# 89C51.net
KiCad netlist of a schematic drawn in Altium Designer
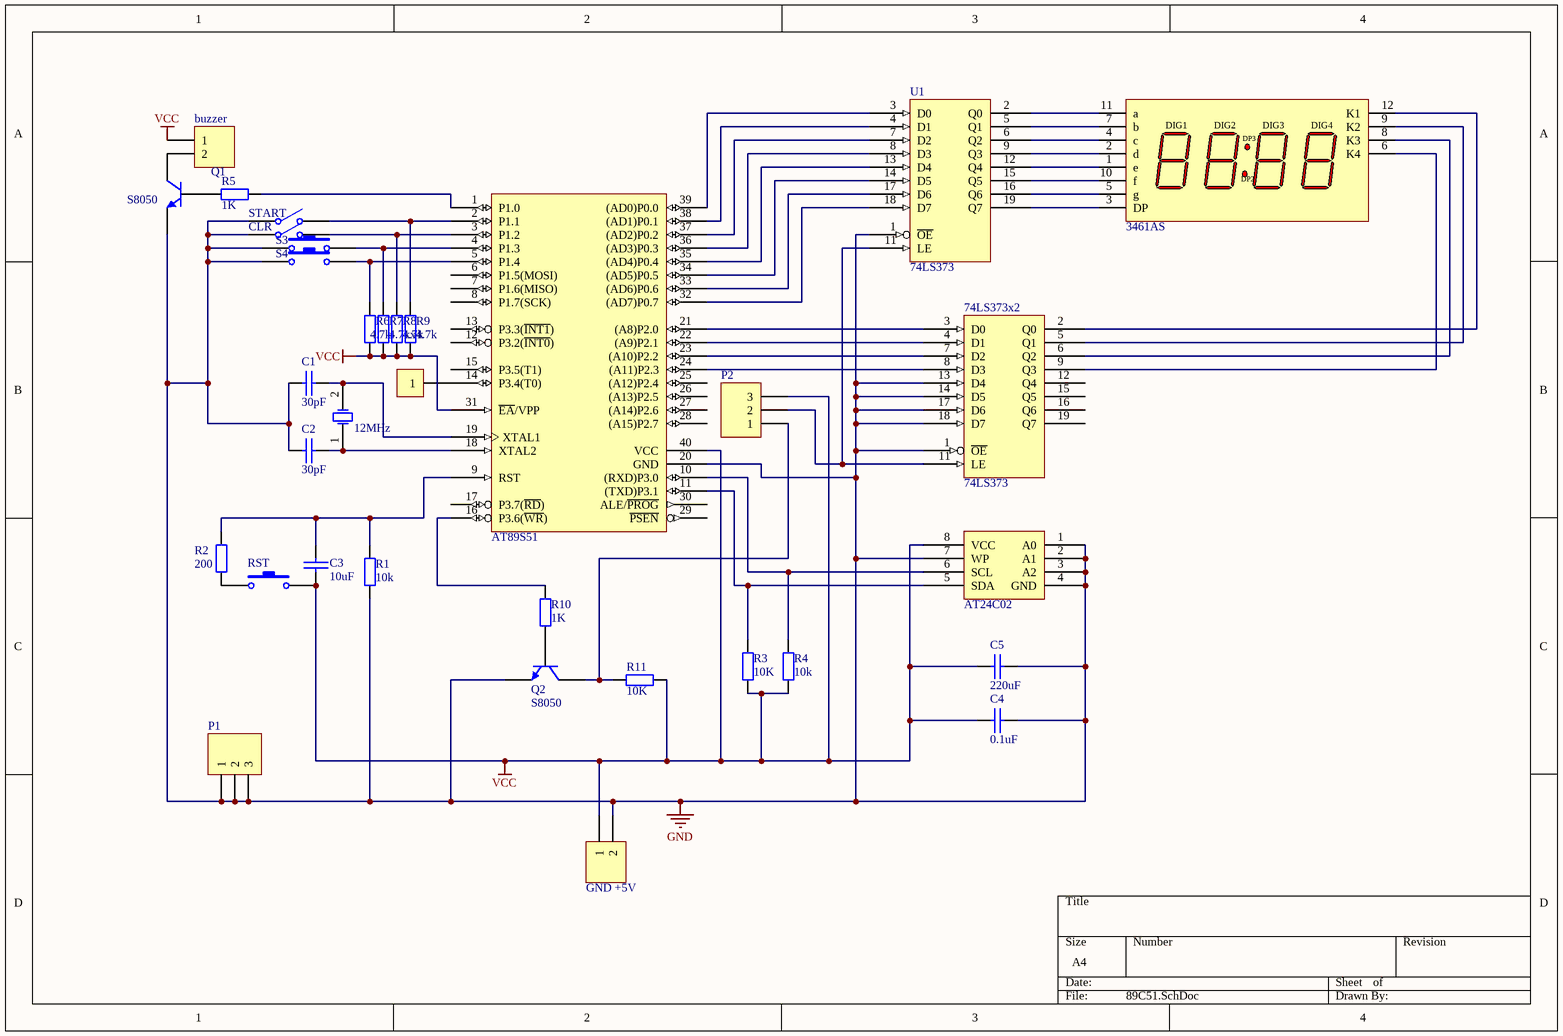
[diagram p0: 89C51.SchDoc]

(export (version "E")
  (design (tool "Eeschema 10.0.6"))
  (components
    (comp (ref "74LS373x2")
      (value "74LS373")
      (footprint "DIP-20")
      (libsource (lib "Protel DOS Schematic TTL") (part "74LS373"))
    )
    (comp (ref "89S51")
      (value "AT89S51")
      (footprint "DIP-40")
      (description "8-Bit Microcontroller with 4K ISP Flash ROM")
      (libsource (lib "Atmel Microcontroller 8051 Architecture") (part "AT89S51"))
    )
    (comp (ref "buzzer")
      (value "Header 2")
      (footprint "BUZZER")
      (description "Header, 2-Pin")
      (fields (field (name "PUBLISHER") "Altium Limited"))
      (libsource (lib "") (part "Header 2_1"))
    )
    (comp (ref "C1")
      (value "30pF")
      (footprint "RAD-0.1")
      (description "Capacitor")
      (libsource (lib "Miscellaneous Devices") (part "CAP"))
    )
    (comp (ref "C2")
      (value "30pF")
      (footprint "RAD-0.1")
      (description "Capacitor")
      (libsource (lib "Miscellaneous Devices") (part "CAP"))
    )
    (comp (ref "C3")
      (value "10uF")
      (footprint "RB.2/.1")
      (description "Capacitor")
      (libsource (lib "Miscellaneous Devices") (part "CAP"))
    )
    (comp (ref "C4")
      (value "0.1uF")
      (footprint "RAD-0.1")
      (description "Capacitor")
      (libsource (lib "Miscellaneous Devices") (part "CAP"))
    )
    (comp (ref "C5")
      (value "220uF")
      (footprint "RB.2/.2")
      (description "Capacitor")
      (libsource (lib "Miscellaneous Devices") (part "CAP"))
    )
    (comp (ref "CLR")
      (value "~")
      (footprint "push_switch")
      (description "Single-Pole, Single-Throw Switch")
      (fields (field (name "PUBLISHER") "Altium Limited"))
      (libsource (lib "Miscellaneous Devices") (part "SW-SPST"))
    )
    (comp (ref "Disp")
      (value "3461AS")
      (footprint "3461AS")
      (description "14.22 mm GaP HER, Untinted, 88:88 4-Digit 7-Segment Display: CC, Gray Surface")
      (fields (field (name "PUBLISHER") "Altium Limited"))
      (libsource (lib "Agilent LED Display 7-Segment, 4-Digit") (part "HDSP-B03E"))
    )
    (comp (ref "GND +5V")
      (value "Header 2")
      (footprint "POWER PLUG2")
      (description "Header, 2-Pin")
      (fields (field (name "PUBLISHER") "Altium Limited"))
      (libsource (lib "Miscellaneous Connectors") (part "Header 2"))
    )
    (comp (ref "header1") (value "HDR_1") (footprint "HDR_1") (libsource (lib "for_use") (part "HDR_1")))
    (comp (ref "P1")
      (value "Header 3")
      (footprint "HDR1X3")
      (description "Header, 3-Pin")
      (fields (field (name "PUBLISHER") "Altium Limited"))
      (libsource (lib "Miscellaneous Connectors") (part "Header 3"))
    )
    (comp (ref "P2")
      (value "Header 3")
      (footprint "HDR1X3")
      (description "Header, 3-Pin")
      (fields (field (name "PUBLISHER") "Altium Limited"))
      (libsource (lib "") (part "Header 3_1"))
    )
    (comp (ref "Q1")
      (value "S8050")
      (footprint "NPN-2")
      (description "NPN General Purpose Amplifier")
      (fields (field (name "PUBLISHER") "Altium Limited"))
      (libsource (lib "Miscellaneous Devices") (part "2N3904"))
    )
    (comp (ref "Q2")
      (value "S8050")
      (footprint "NPN-2")
      (description "NPN General Purpose Amplifier")
      (fields (field (name "PUBLISHER") "Altium Limited"))
      (libsource (lib "") (part "2N3904_1"))
    )
    (comp (ref "R1")
      (value "10k")
      (footprint "AXIAL-0.4")
      (description "Resistor")
      (fields (field (name "COMMENT_1") "10k") (field (name "PUBLISHER") "Altium Limited"))
      (libsource (lib "Miscellaneous Devices") (part "Res2"))
    )
    (comp (ref "R2")
      (value "200")
      (footprint "AXIAL-0.4")
      (description "Resistor")
      (fields (field (name "PUBLISHER") "Altium Limited"))
      (libsource (lib "Miscellaneous Devices") (part "Res2"))
    )
    (comp (ref "R3")
      (value "10K")
      (footprint "AXIAL-0.4")
      (description "Resistor")
      (fields (field (name "PUBLISHER") "Altium Limited"))
      (libsource (lib "Miscellaneous Devices") (part "Res2"))
    )
    (comp (ref "R4")
      (value "10k")
      (footprint "AXIAL-0.4")
      (description "Resistor")
      (fields (field (name "Comment") "10K") (field (name "PUBLISHER") "Altium Limited"))
      (libsource (lib "Miscellaneous Devices") (part "Res2"))
    )
    (comp (ref "R5")
      (value "1K")
      (footprint "AXIAL-0.4")
      (description "Resistor")
      (fields (field (name "PUBLISHER") "Altium Limited"))
      (libsource (lib "") (part "Res2_1"))
    )
    (comp (ref "R6")
      (value "4.7k")
      (footprint "AXIAL-0.4")
      (description "Resistor")
      (fields (field (name "PUBLISHER") "Altium Limited"))
      (libsource (lib "Miscellaneous Devices") (part "Res2"))
    )
    (comp (ref "R7")
      (value "4.7kx4")
      (footprint "AXIAL-0.4")
      (description "Resistor")
      (fields (field (name "PUBLISHER") "Altium Limited"))
      (libsource (lib "Miscellaneous Devices") (part "Res2"))
    )
    (comp (ref "R8")
      (value "4.7k")
      (footprint "AXIAL-0.4")
      (description "Resistor")
      (fields (field (name "PUBLISHER") "Altium Limited"))
      (libsource (lib "Miscellaneous Devices") (part "Res2"))
    )
    (comp (ref "R9")
      (value "4.7k")
      (footprint "AXIAL-0.4")
      (description "Resistor")
      (fields (field (name "PUBLISHER") "Altium Limited"))
      (libsource (lib "Miscellaneous Devices") (part "Res2"))
    )
    (comp (ref "R10")
      (value "1K")
      (footprint "AXIAL-0.4")
      (description "Resistor")
      (fields (field (name "PUBLISHER") "Altium Limited"))
      (libsource (lib "Miscellaneous Devices") (part "Res2"))
    )
    (comp (ref "R11")
      (value "10K")
      (footprint "AXIAL-0.4")
      (description "Resistor")
      (fields (field (name "PUBLISHER") "Altium Limited"))
      (libsource (lib "") (part "Res2_2"))
    )
    (comp (ref "RST")
      (value "SW-PB")
      (footprint "AN-S")
      (description "Switch")
      (fields (field (name "PUBLISHER") "Altium Limited"))
      (libsource (lib "Miscellaneous Devices") (part "SW-PB"))
    )
    (comp (ref "S3")
      (value "SW-PB")
      (footprint "AN-S")
      (description "Switch")
      (fields (field (name "PUBLISHER") "Altium Limited"))
      (libsource (lib "Miscellaneous Devices") (part "SW-PB"))
    )
    (comp (ref "S4")
      (value "SW-PB")
      (footprint "AN-S")
      (description "Switch")
      (fields (field (name "PUBLISHER") "Altium Limited"))
      (libsource (lib "Miscellaneous Devices") (part "SW-PB"))
    )
    (comp (ref "START")
      (value "~")
      (footprint "push_switch")
      (description "Single-Pole, Single-Throw Switch")
      (fields (field (name "PUBLISHER") "Altium Limited"))
      (libsource (lib "Miscellaneous Devices") (part "SW-SPST"))
    )
    (comp (ref "U1")
      (value "74LS373")
      (footprint "DIP-20")
      (libsource (lib "Protel DOS Schematic TTL") (part "74LS373"))
    )
    (comp (ref "U4") (value "AT24C02") (footprint "DIP-8") (libsource (lib "for_use") (part "AT24C02")))
    (comp (ref "Y1")
      (value "12MHz")
      (footprint "XTAL-1")
      (description "Crystal Oscillator")
      (fields (field (name "PUBLISHER") "Altium Limited"))
      (libsource (lib "Miscellaneous Devices") (part "XTAL"))
    )
  )
  (nets
    (net (code "1") (name "GND") (class "Default")
      (node (ref "74LS373x2") (pin "1") (pinfunction "~{OE}_1") (pintype "input"))
      (node (ref "74LS373x2") (pin "10") (pinfunction "GND_10") (pintype "power_in"))
      (node (ref "74LS373x2") (pin "13") (pinfunction "D4_13") (pintype "input"))
      (node (ref "74LS373x2") (pin "14") (pinfunction "D5_14") (pintype "input"))
      (node (ref "74LS373x2") (pin "17") (pinfunction "D6_17") (pintype "input"))
      (node (ref "74LS373x2") (pin "18") (pinfunction "D7_18") (pintype "input"))
      (node (ref "89S51") (pin "20") (pinfunction "GND_20") (pintype "power_in"))
      (node (ref "C1") (pin "1") (pinfunction "1_1") (pintype "passive"))
      (node (ref "C2") (pin "1") (pinfunction "1_1") (pintype "passive"))
      (node (ref "C4") (pin "2") (pinfunction "2_2") (pintype "passive"))
      (node (ref "C5") (pin "2") (pinfunction "2_2") (pintype "passive"))
      (node (ref "CLR") (pin "1") (pinfunction "COMMON_1") (pintype "passive"))
      (node (ref "GND +5V") (pin "2") (pinfunction "2_2") (pintype "passive"))
      (node (ref "P1") (pin "1") (pinfunction "1_1") (pintype "passive"))
      (node (ref "P1") (pin "2") (pinfunction "2_2") (pintype "passive"))
      (node (ref "P1") (pin "3") (pinfunction "3_3") (pintype "passive"))
      (node (ref "Q1") (pin "1") (pinfunction "E_1") (pintype "passive"))
      (node (ref "Q2") (pin "1") (pinfunction "E_1") (pintype "passive"))
      (node (ref "R1") (pin "1") (pinfunction "1_1") (pintype "passive"))
      (node (ref "S3") (pin "1") (pinfunction "1_1") (pintype "passive"))
      (node (ref "S4") (pin "1") (pinfunction "1_1") (pintype "passive"))
      (node (ref "START") (pin "1") (pinfunction "COMMON_1") (pintype "passive"))
      (node (ref "U1") (pin "1") (pinfunction "~{OE}_1") (pintype "input"))
      (node (ref "U1") (pin "10") (pinfunction "GND_10") (pintype "power_in"))
      (node (ref "U4") (pin "1") (pinfunction "A0_1") (pintype "passive"))
      (node (ref "U4") (pin "2") (pinfunction "A1_2") (pintype "passive"))
      (node (ref "U4") (pin "3") (pinfunction "A2_3") (pintype "passive"))
      (node (ref "U4") (pin "4") (pinfunction "GND_4") (pintype "passive"))
      (node (ref "U4") (pin "7") (pinfunction "WP_7") (pintype "passive"))
    )
    (net (code "2") (name "Net-(74LS373x2-D0)") (class "Default")
      (node (ref "74LS373x2") (pin "3") (pinfunction "D0_3") (pintype "input"))
      (node (ref "89S51") (pin "21") (pinfunction "(A8)P2.0_21") (pintype "bidirectional"))
    )
    (net (code "3") (name "Net-(74LS373x2-D1)") (class "Default")
      (node (ref "74LS373x2") (pin "4") (pinfunction "D1_4") (pintype "input"))
      (node (ref "89S51") (pin "22") (pinfunction "(A9)P2.1_22") (pintype "bidirectional"))
    )
    (net (code "4") (name "Net-(74LS373x2-D2)") (class "Default")
      (node (ref "74LS373x2") (pin "7") (pinfunction "D2_7") (pintype "input"))
      (node (ref "89S51") (pin "23") (pinfunction "(A10)P2.2_23") (pintype "bidirectional"))
    )
    (net (code "5") (name "Net-(74LS373x2-D3)") (class "Default")
      (node (ref "74LS373x2") (pin "8") (pinfunction "D3_8") (pintype "input"))
      (node (ref "89S51") (pin "24") (pinfunction "(A11)P2.3_24") (pintype "bidirectional"))
    )
    (net (code "6") (name "Net-(74LS373x2-LE)") (class "Default")
      (node (ref "74LS373x2") (pin "11") (pinfunction "LE_11") (pintype "input"))
      (node (ref "P2") (pin "2") (pinfunction "2_2") (pintype "passive"))
      (node (ref "U1") (pin "11") (pinfunction "LE_11") (pintype "input"))
    )
    (net (code "7") (name "Net-(74LS373x2-Q0)") (class "Default")
      (node (ref "74LS373x2") (pin "2") (pinfunction "Q0_2") (pintype "tri_state"))
      (node (ref "Disp") (pin "12") (pinfunction "K1_12") (pintype "passive"))
    )
    (net (code "8") (name "Net-(74LS373x2-Q1)") (class "Default")
      (node (ref "74LS373x2") (pin "5") (pinfunction "Q1_5") (pintype "tri_state"))
      (node (ref "Disp") (pin "9") (pinfunction "K2_9") (pintype "passive"))
    )
    (net (code "9") (name "Net-(74LS373x2-Q2)") (class "Default")
      (node (ref "74LS373x2") (pin "6") (pinfunction "Q2_6") (pintype "tri_state"))
      (node (ref "Disp") (pin "8") (pinfunction "K3_8") (pintype "passive"))
    )
    (net (code "10") (name "Net-(74LS373x2-Q3)") (class "Default")
      (node (ref "74LS373x2") (pin "9") (pinfunction "Q3_9") (pintype "tri_state"))
      (node (ref "Disp") (pin "6") (pinfunction "K4_6") (pintype "passive"))
    )
    (net (code "11") (name "Net-(89S51-(AD0)P0.0)") (class "Default")
      (node (ref "89S51") (pin "39") (pinfunction "(AD0)P0.0_39") (pintype "bidirectional"))
      (node (ref "U1") (pin "3") (pinfunction "D0_3") (pintype "input"))
    )
    (net (code "12") (name "Net-(89S51-(AD1)P0.1)") (class "Default")
      (node (ref "89S51") (pin "38") (pinfunction "(AD1)P0.1_38") (pintype "bidirectional"))
      (node (ref "U1") (pin "4") (pinfunction "D1_4") (pintype "input"))
    )
    (net (code "13") (name "Net-(89S51-(AD2)P0.2)") (class "Default")
      (node (ref "89S51") (pin "37") (pinfunction "(AD2)P0.2_37") (pintype "bidirectional"))
      (node (ref "U1") (pin "7") (pinfunction "D2_7") (pintype "input"))
    )
    (net (code "14") (name "Net-(89S51-(AD3)P0.3)") (class "Default")
      (node (ref "89S51") (pin "36") (pinfunction "(AD3)P0.3_36") (pintype "bidirectional"))
      (node (ref "U1") (pin "8") (pinfunction "D3_8") (pintype "input"))
    )
    (net (code "15") (name "Net-(89S51-(AD4)P0.4)") (class "Default")
      (node (ref "89S51") (pin "35") (pinfunction "(AD4)P0.4_35") (pintype "bidirectional"))
      (node (ref "U1") (pin "13") (pinfunction "D4_13") (pintype "input"))
    )
    (net (code "16") (name "Net-(89S51-(AD5)P0.5)") (class "Default")
      (node (ref "89S51") (pin "34") (pinfunction "(AD5)P0.5_34") (pintype "bidirectional"))
      (node (ref "U1") (pin "14") (pinfunction "D5_14") (pintype "input"))
    )
    (net (code "17") (name "Net-(89S51-(AD6)P0.6)") (class "Default")
      (node (ref "89S51") (pin "33") (pinfunction "(AD6)P0.6_33") (pintype "bidirectional"))
      (node (ref "U1") (pin "17") (pinfunction "D6_17") (pintype "input"))
    )
    (net (code "18") (name "Net-(89S51-(AD7)P0.7)") (class "Default")
      (node (ref "89S51") (pin "32") (pinfunction "(AD7)P0.7_32") (pintype "bidirectional"))
      (node (ref "U1") (pin "18") (pinfunction "D7_18") (pintype "input"))
    )
    (net (code "19") (name "Net-(89S51-(RXD)P3.0)") (class "Default")
      (node (ref "89S51") (pin "10") (pinfunction "(RXD)P3.0_10") (pintype "bidirectional"))
      (node (ref "R4") (pin "2") (pinfunction "2_2") (pintype "passive"))
      (node (ref "U4") (pin "6") (pinfunction "SCL_6") (pintype "passive"))
    )
    (net (code "20") (name "Net-(89S51-(TXD)P3.1)") (class "Default")
      (node (ref "89S51") (pin "11") (pinfunction "(TXD)P3.1_11") (pintype "bidirectional"))
      (node (ref "R3") (pin "2") (pinfunction "2_2") (pintype "passive"))
      (node (ref "U4") (pin "5") (pinfunction "SDA_5") (pintype "passive"))
    )
    (net (code "21") (name "Net-(89S51-P1.0)") (class "Default")
      (node (ref "89S51") (pin "1") (pinfunction "P1.0_1") (pintype "bidirectional"))
      (node (ref "R5") (pin "1") (pinfunction "1_1") (pintype "passive"))
    )
    (net (code "22") (name "Net-(89S51-P1.1)") (class "Default")
      (node (ref "89S51") (pin "2") (pinfunction "P1.1_2") (pintype "bidirectional"))
      (node (ref "R9") (pin "2") (pinfunction "2_2") (pintype "passive"))
      (node (ref "START") (pin "2") (pinfunction "NO_2") (pintype "passive"))
    )
    (net (code "23") (name "Net-(89S51-P1.2)") (class "Default")
      (node (ref "89S51") (pin "3") (pinfunction "P1.2_3") (pintype "bidirectional"))
      (node (ref "CLR") (pin "2") (pinfunction "NO_2") (pintype "passive"))
      (node (ref "R8") (pin "2") (pinfunction "2_2") (pintype "passive"))
    )
    (net (code "24") (name "Net-(89S51-P1.3)") (class "Default")
      (node (ref "89S51") (pin "4") (pinfunction "P1.3_4") (pintype "bidirectional"))
      (node (ref "R7") (pin "2") (pinfunction "2_2") (pintype "passive"))
      (node (ref "S3") (pin "2") (pinfunction "2_2") (pintype "passive"))
    )
    (net (code "25") (name "Net-(89S51-P1.4)") (class "Default")
      (node (ref "89S51") (pin "5") (pinfunction "P1.4_5") (pintype "bidirectional"))
      (node (ref "R6") (pin "2") (pinfunction "2_2") (pintype "passive"))
      (node (ref "S4") (pin "2") (pinfunction "2_2") (pintype "passive"))
    )
    (net (code "26") (name "Net-(89S51-P3.4(T0))") (class "Default")
      (node (ref "89S51") (pin "14") (pinfunction "P3.4(T0)_14") (pintype "bidirectional"))
      (node (ref "header1") (pin "1") (pinfunction "1_1") (pintype "passive"))
    )
    (net (code "27") (name "Net-(89S51-P3.6(~{WR}))") (class "Default")
      (node (ref "89S51") (pin "16") (pinfunction "P3.6(~{WR})_16") (pintype "bidirectional"))
      (node (ref "R10") (pin "2") (pinfunction "2_2") (pintype "passive"))
    )
    (net (code "28") (name "Net-(89S51-RST)") (class "Default")
      (node (ref "89S51") (pin "9") (pinfunction "RST_9") (pintype "input"))
      (node (ref "C3") (pin "2") (pinfunction "2_2") (pintype "passive"))
      (node (ref "R1") (pin "2") (pinfunction "2_2") (pintype "passive"))
      (node (ref "R2") (pin "2") (pinfunction "2_2") (pintype "passive"))
    )
    (net (code "29") (name "Net-(89S51-XTAL1)") (class "Default")
      (node (ref "89S51") (pin "19") (pinfunction "XTAL1_19") (pintype "input"))
      (node (ref "C1") (pin "2") (pinfunction "2_2") (pintype "passive"))
      (node (ref "Y1") (pin "2") (pinfunction "OSC2_2") (pintype "passive"))
    )
    (net (code "30") (name "Net-(89S51-XTAL2)") (class "Default")
      (node (ref "89S51") (pin "18") (pinfunction "XTAL2_18") (pintype "input"))
      (node (ref "C2") (pin "2") (pinfunction "2_2") (pintype "passive"))
      (node (ref "Y1") (pin "1") (pinfunction "OSC1_1") (pintype "passive"))
    )
    (net (code "31") (name "Net-(Disp-DP)") (class "Default")
      (node (ref "Disp") (pin "3") (pinfunction "DP_3") (pintype "passive"))
      (node (ref "U1") (pin "19") (pinfunction "Q7_19") (pintype "tri_state"))
    )
    (net (code "32") (name "Net-(Disp-a)") (class "Default")
      (node (ref "Disp") (pin "11") (pinfunction "a_11") (pintype "passive"))
      (node (ref "U1") (pin "2") (pinfunction "Q0_2") (pintype "tri_state"))
    )
    (net (code "33") (name "Net-(Disp-b)") (class "Default")
      (node (ref "Disp") (pin "7") (pinfunction "b_7") (pintype "passive"))
      (node (ref "U1") (pin "5") (pinfunction "Q1_5") (pintype "tri_state"))
    )
    (net (code "34") (name "Net-(Disp-c)") (class "Default")
      (node (ref "Disp") (pin "4") (pinfunction "c_4") (pintype "passive"))
      (node (ref "U1") (pin "6") (pinfunction "Q2_6") (pintype "tri_state"))
    )
    (net (code "35") (name "Net-(Disp-d)") (class "Default")
      (node (ref "Disp") (pin "2") (pinfunction "d_2") (pintype "passive"))
      (node (ref "U1") (pin "9") (pinfunction "Q3_9") (pintype "tri_state"))
    )
    (net (code "36") (name "Net-(Disp-e)") (class "Default")
      (node (ref "Disp") (pin "1") (pinfunction "e_1") (pintype "passive"))
      (node (ref "U1") (pin "12") (pinfunction "Q4_12") (pintype "tri_state"))
    )
    (net (code "37") (name "Net-(Disp-f)") (class "Default")
      (node (ref "Disp") (pin "10") (pinfunction "f_10") (pintype "passive"))
      (node (ref "U1") (pin "15") (pinfunction "Q5_15") (pintype "tri_state"))
    )
    (net (code "38") (name "Net-(Disp-g)") (class "Default")
      (node (ref "Disp") (pin "5") (pinfunction "g_5") (pintype "passive"))
      (node (ref "U1") (pin "16") (pinfunction "Q6_16") (pintype "tri_state"))
    )
    (net (code "39") (name "Net-(Q1-B)") (class "Default")
      (node (ref "Q1") (pin "2") (pinfunction "B_2") (pintype "passive"))
      (node (ref "R5") (pin "2") (pinfunction "2_2") (pintype "passive"))
    )
    (net (code "40") (name "Net-(Q1-C)") (class "Default")
      (node (ref "Q1") (pin "3") (pinfunction "C_3") (pintype "passive"))
      (node (ref "buzzer") (pin "2") (pinfunction "2_2") (pintype "passive"))
    )
    (net (code "41") (name "Net-(Q2-B)") (class "Default")
      (node (ref "Q2") (pin "2") (pinfunction "B_2") (pintype "passive"))
      (node (ref "R10") (pin "1") (pinfunction "1_1") (pintype "passive"))
    )
    (net (code "42") (name "Net-(Q2-C)") (class "Default")
      (node (ref "P2") (pin "1") (pinfunction "1_1") (pintype "passive"))
      (node (ref "Q2") (pin "3") (pinfunction "C_3") (pintype "passive"))
      (node (ref "R11") (pin "1") (pinfunction "1_1") (pintype "passive"))
    )
    (net (code "43") (name "Net-(R2-Pad1)") (class "Default")
      (node (ref "R2") (pin "1") (pinfunction "1_1") (pintype "passive"))
      (node (ref "RST") (pin "1") (pinfunction "1_1") (pintype "passive"))
    )
    (net (code "44") (name "VCC") (class "Default")
      (node (ref "74LS373x2") (pin "20") (pinfunction "VCC_20") (pintype "power_in"))
      (node (ref "89S51") (pin "31") (pinfunction "~{EA}/VPP_31") (pintype "input"))
      (node (ref "89S51") (pin "40") (pinfunction "VCC_40") (pintype "power_in"))
      (node (ref "C3") (pin "1") (pinfunction "1_1") (pintype "passive"))
      (node (ref "C4") (pin "1") (pinfunction "1_1") (pintype "passive"))
      (node (ref "C5") (pin "1") (pinfunction "1_1") (pintype "passive"))
      (node (ref "GND +5V") (pin "1") (pinfunction "1_1") (pintype "passive"))
      (node (ref "P2") (pin "3") (pinfunction "3_3") (pintype "passive"))
      (node (ref "R11") (pin "2") (pinfunction "2_2") (pintype "passive"))
      (node (ref "R3") (pin "1") (pinfunction "1_1") (pintype "passive"))
      (node (ref "R4") (pin "1") (pinfunction "1_1") (pintype "passive"))
      (node (ref "R6") (pin "1") (pinfunction "1_1") (pintype "passive"))
      (node (ref "R7") (pin "1") (pinfunction "1_1") (pintype "passive"))
      (node (ref "R8") (pin "1") (pinfunction "1_1") (pintype "passive"))
      (node (ref "R9") (pin "1") (pinfunction "1_1") (pintype "passive"))
      (node (ref "RST") (pin "2") (pinfunction "2_2") (pintype "passive"))
      (node (ref "U1") (pin "20") (pinfunction "VCC_20") (pintype "power_in"))
      (node (ref "U4") (pin "8") (pinfunction "VCC_8") (pintype "passive"))
      (node (ref "buzzer") (pin "1") (pinfunction "1_1") (pintype "passive"))
    )
    (net (code "45") (name "unconnected-(74LS373x2-Q4-Pad12)") (class "Default")
      (node (ref "74LS373x2") (pin "12") (pinfunction "Q4_12") (pintype "tri_state"))
    )
    (net (code "46") (name "unconnected-(74LS373x2-Q5-Pad15)") (class "Default")
      (node (ref "74LS373x2") (pin "15") (pinfunction "Q5_15") (pintype "tri_state"))
    )
    (net (code "47") (name "unconnected-(74LS373x2-Q6-Pad16)") (class "Default")
      (node (ref "74LS373x2") (pin "16") (pinfunction "Q6_16") (pintype "tri_state"))
    )
    (net (code "48") (name "unconnected-(74LS373x2-Q7-Pad19)") (class "Default")
      (node (ref "74LS373x2") (pin "19") (pinfunction "Q7_19") (pintype "tri_state"))
    )
    (net (code "49") (name "unconnected-(89S51-(A12)P2.4-Pad25)") (class "Default")
      (node (ref "89S51") (pin "25") (pinfunction "(A12)P2.4_25") (pintype "bidirectional"))
    )
    (net (code "50") (name "unconnected-(89S51-(A13)P2.5-Pad26)") (class "Default")
      (node (ref "89S51") (pin "26") (pinfunction "(A13)P2.5_26") (pintype "bidirectional"))
    )
    (net (code "51") (name "unconnected-(89S51-(A14)P2.6-Pad27)") (class "Default")
      (node (ref "89S51") (pin "27") (pinfunction "(A14)P2.6_27") (pintype "bidirectional"))
    )
    (net (code "52") (name "unconnected-(89S51-(A15)P2.7-Pad28)") (class "Default")
      (node (ref "89S51") (pin "28") (pinfunction "(A15)P2.7_28") (pintype "bidirectional"))
    )
    (net (code "53") (name "unconnected-(89S51-ALE{slash}~{PROG}-Pad30)") (class "Default")
      (node (ref "89S51") (pin "30") (pinfunction "ALE/~{PROG}_30") (pintype "output"))
    )
    (net (code "54") (name "unconnected-(89S51-P1.5(MOSI)-Pad6)") (class "Default")
      (node (ref "89S51") (pin "6") (pinfunction "P1.5(MOSI)_6") (pintype "bidirectional"))
    )
    (net (code "55") (name "unconnected-(89S51-P1.6(MISO)-Pad7)") (class "Default")
      (node (ref "89S51") (pin "7") (pinfunction "P1.6(MISO)_7") (pintype "bidirectional"))
    )
    (net (code "56") (name "unconnected-(89S51-P1.7(SCK)-Pad8)") (class "Default")
      (node (ref "89S51") (pin "8") (pinfunction "P1.7(SCK)_8") (pintype "bidirectional"))
    )
    (net (code "57") (name "unconnected-(89S51-P3.2(~{INT0})-Pad12)") (class "Default")
      (node (ref "89S51") (pin "12") (pinfunction "P3.2(~{INT0})_12") (pintype "bidirectional"))
    )
    (net (code "58") (name "unconnected-(89S51-P3.3(~{INT1})-Pad13)") (class "Default")
      (node (ref "89S51") (pin "13") (pinfunction "P3.3(~{INT1})_13") (pintype "bidirectional"))
    )
    (net (code "59") (name "unconnected-(89S51-P3.5(T1)-Pad15)") (class "Default")
      (node (ref "89S51") (pin "15") (pinfunction "P3.5(T1)_15") (pintype "bidirectional"))
    )
    (net (code "60") (name "unconnected-(89S51-P3.7(~{RD})-Pad17)") (class "Default")
      (node (ref "89S51") (pin "17") (pinfunction "P3.7(~{RD})_17") (pintype "bidirectional"))
    )
    (net (code "61") (name "unconnected-(89S51-~{PSEN}-Pad29)") (class "Default")
      (node (ref "89S51") (pin "29") (pinfunction "~{PSEN}_29") (pintype "output"))
    )
  )
)
